# PiZero2W_Hat.net
KiCad netlist of a schematic drawn in Altium Designer
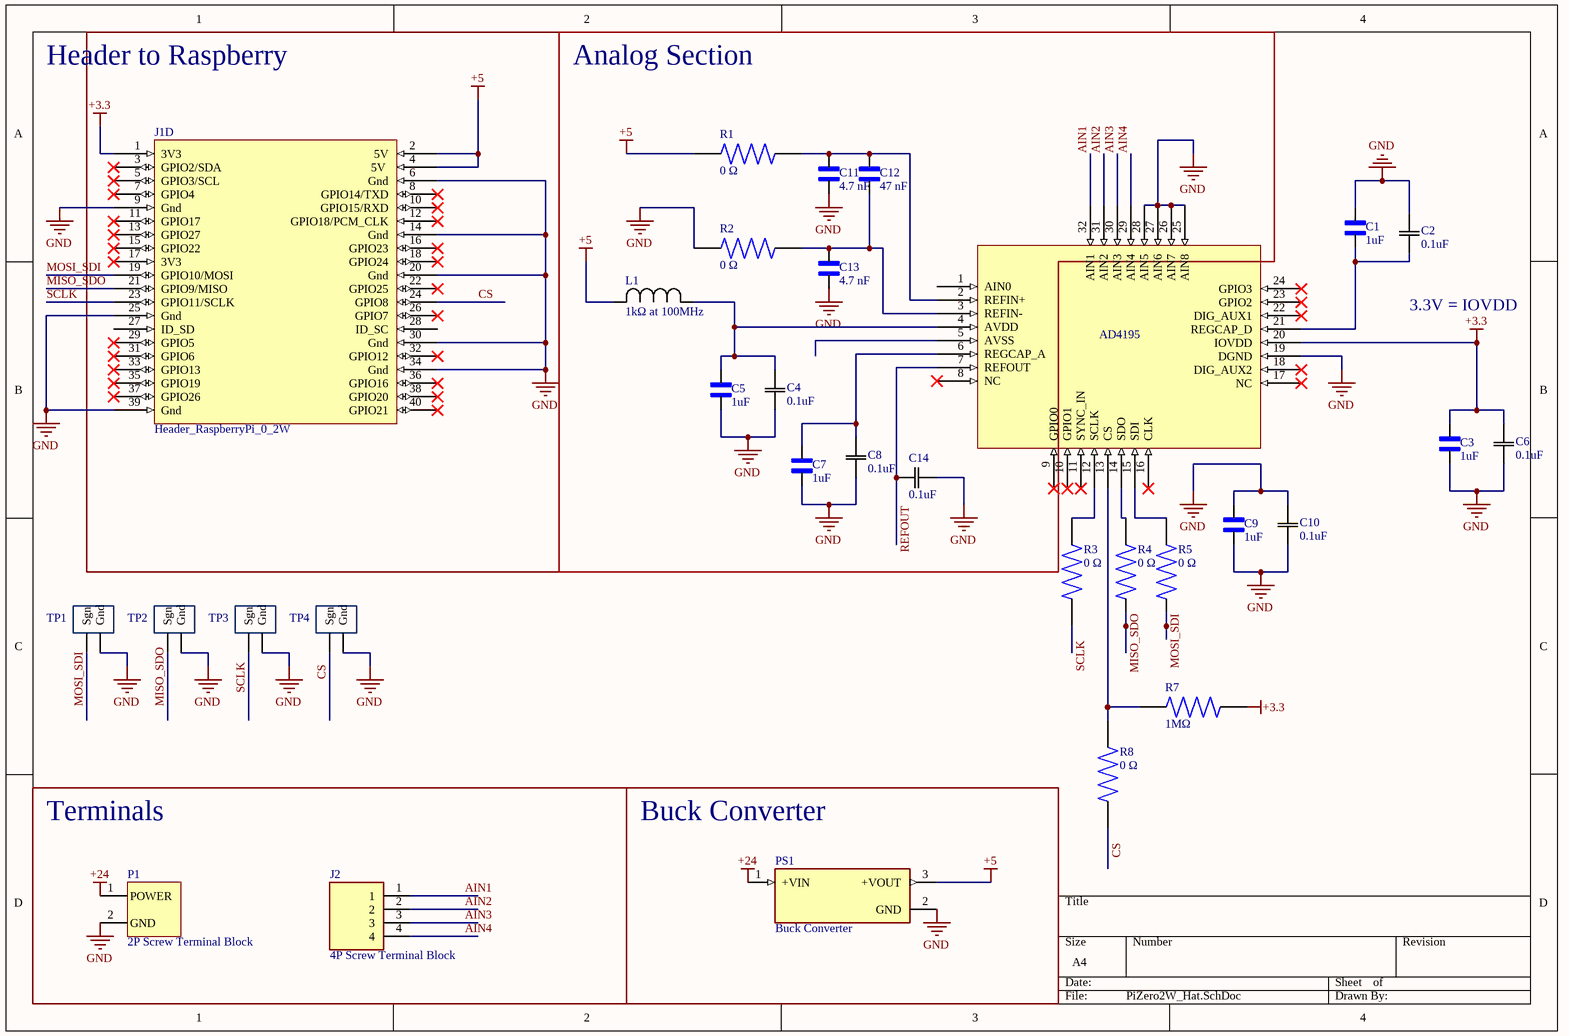
[diagram p0: PiZero2W_Hat.SchDoc]

(export (version "E")
  (design (tool "Eeschema 10.0.6"))
  (components
    (comp (ref "AD4195")
      (value "omponent_1")
      (footprint "QFN50P400X600X80_HS-33N")
      (libsource (lib "RaspberryPi_Zero_2W") (part "Component_1"))
    )
    (comp (ref "C1")
      (value "1uF")
      (footprint "CAPC1608X90N")
      (fields (field (name "MP") "C0603C105K4RACTU"))
      (libsource (lib "C0603C105K4RACTU") (part "C0603C105K4RACTU"))
    )
    (comp (ref "C2")
      (value "0.1uF")
      (footprint "0402_AVX")
      (description "Description")
      (fields
        (field (name "MANUFACTURER_PART_NUMBER") "04023C104KAT2A")
        (field (name "COPYRIGHT") "Copyright (C) 2025 Ultra Librarian. All rights reserved.")
      )
      (libsource (lib "Integrated_Library2") (part "04023C104KAT2A"))
    )
    (comp (ref "C3")
      (value "1uF")
      (footprint "CAPC1608X90N")
      (fields (field (name "MP") "C0603C105K4RACTU"))
      (libsource (lib "C0603C105K4RACTU") (part "C0603C105K4RACTU"))
    )
    (comp (ref "C4")
      (value "0.1uF")
      (footprint "0402_AVX")
      (description "Description")
      (fields
        (field (name "MANUFACTURER_PART_NUMBER") "04023C104KAT2A")
        (field (name "COPYRIGHT") "Copyright (C) 2025 Ultra Librarian. All rights reserved.")
      )
      (libsource (lib "Integrated_Library2") (part "04023C104KAT2A"))
    )
    (comp (ref "C5")
      (value "1uF")
      (footprint "CAPC1608X90N")
      (fields (field (name "MP") "C0603C105K4RACTU"))
      (libsource (lib "C0603C105K4RACTU") (part "C0603C105K4RACTU"))
    )
    (comp (ref "C6")
      (value "0.1uF")
      (footprint "0402_AVX")
      (description "Description")
      (fields
        (field (name "MANUFACTURER_PART_NUMBER") "04023C104KAT2A")
        (field (name "COPYRIGHT") "Copyright (C) 2025 Ultra Librarian. All rights reserved.")
      )
      (libsource (lib "Integrated_Library2") (part "04023C104KAT2A"))
    )
    (comp (ref "C7")
      (value "1uF")
      (footprint "CAPC1608X90N")
      (fields (field (name "MP") "C0603C105K4RACTU"))
      (libsource (lib "C0603C105K4RACTU") (part "C0603C105K4RACTU"))
    )
    (comp (ref "C8")
      (value "0.1uF")
      (footprint "0402_AVX")
      (description "Description")
      (fields
        (field (name "MANUFACTURER_PART_NUMBER") "04023C104KAT2A")
        (field (name "COPYRIGHT") "Copyright (C) 2025 Ultra Librarian. All rights reserved.")
      )
      (libsource (lib "Integrated_Library2") (part "04023C104KAT2A"))
    )
    (comp (ref "C9")
      (value "1uF")
      (footprint "CAPC1608X90N")
      (fields (field (name "MP") "C0603C105K4RACTU"))
      (libsource (lib "C0603C105K4RACTU") (part "C0603C105K4RACTU"))
    )
    (comp (ref "C10")
      (value "0.1uF")
      (footprint "0402_AVX")
      (description "Description")
      (fields
        (field (name "MANUFACTURER_PART_NUMBER") "04023C104KAT2A")
        (field (name "COPYRIGHT") "Copyright (C) 2025 Ultra Librarian. All rights reserved.")
      )
      (libsource (lib "Integrated_Library2") (part "04023C104KAT2A"))
    )
    (comp (ref "C11")
      (value "4.7 nF")
      (footprint "CAPC1608X90N")
      (description "0603 4.7 nF 50 V Â±5% Tolerance C0G SMT Multilayer Ceramic Capacitor")
      (fields (field (name "MF") "Murata") (field (name "MP") "GRM1885C1H472JA01D"))
      (libsource (lib "GRM1885C1H472JA01D") (part "GRM1885C1H472JA01D"))
    )
    (comp (ref "C12")
      (value "47 nF")
      (footprint "CAPC1005X55N")
      (description "SMD capacitor X7R(EIA) with capacitance 47000pF Tol.10%. Rated voltage 25Vdc 125C")
      (fields (field (name "MF") "Murata") (field (name "MP") "GRM155R71E473KA88D"))
      (libsource (lib "GRM155R71E473KA88D") (part "GRM155R71E473KA88D"))
    )
    (comp (ref "C13")
      (value "4.7 nF")
      (footprint "CAPC1608X90N")
      (description "0603 4.7 nF 50 V Â±5% Tolerance C0G SMT Multilayer Ceramic Capacitor")
      (fields (field (name "MF") "Murata") (field (name "MP") "GRM1885C1H472JA01D"))
      (libsource (lib "GRM1885C1H472JA01D") (part "GRM1885C1H472JA01D"))
    )
    (comp (ref "C14")
      (value "0.1uF")
      (footprint "0402_AVX")
      (description "Description")
      (fields
        (field (name "MANUFACTURER_PART_NUMBER") "04023C104KAT2A")
        (field (name "COPYRIGHT") "Copyright (C) 2025 Ultra Librarian. All rights reserved.")
      )
      (libsource (lib "Integrated_Library2") (part "04023C104KAT2A"))
    )
    (comp (ref "J1")
      (value "Header_RaspberryPi_0_2W")
      (footprint "Edge Connector")
      (libsource (lib "Header_RaspberryPiZero_2W") (part "Header_RaspberryPi_0_2W"))
    )
    (comp (ref "J2")
      (value "4P Screw Terminal Block")
      (footprint "TE_282834-4")
      (fields (field (name "MF") "TE Connectivity") (field (name "MP") "282834-4"))
      (libsource (lib "282834-4") (part "282834-4"))
    )
    (comp (ref "L1")
      (value "1kΩ at 100MHz")
      (footprint "IND_1608_TDK")
      (description "Description")
      (fields
        (field (name "MANUFACTURER_PART_NUMBER") "MPZ1608S102ATA00")
        (field (name "COPYRIGHT") "Copyright (C) 2025 Ultra Librarian. All rights reserved.")
      )
      (libsource (lib "Integrated_Library2") (part "MPZ1608S102ATA00"))
    )
    (comp (ref "P1")
      (value "2P Screw Terminal Block")
      (footprint "P_Terminal block 3.5mm-pitch")
      (description "Green Straight pin 3.5mm  pitch; P=3.5mm  Screw terminal ROHS")
      (fields (field (name "MFR PART #") "KF350-3.5-2P") (field (name "MANUFACTURER") "Cixi Kefa Elec"))
      (libsource (lib "ECEN5730Lib_2023_05_DS") (part "P_Terminal block"))
    )
    (comp (ref "PS1")
      (value "Buck Converter")
      (footprint "CONV_TSR_2-2450N")
      (fields (field (name "MF") "{'manufacturer': u'Traco Power'}") (field (name "MP") "TSR_2-2450N"))
      (libsource (lib "TSR_2-2450N") (part "TSR_2-2450N"))
    )
    (comp (ref "R1")
      (value "0 Ω")
      (footprint "RES_ERJ-2GE0R00X")
      (fields (field (name "MF") "Panasonic") (field (name "MP") "ERJ-2GE0R00X"))
      (libsource (lib "ERJ-2GE0R00X") (part "ERJ-2GE0R00X"))
    )
    (comp (ref "R2")
      (value "0 Ω")
      (footprint "RES_ERJ-2GE0R00X")
      (fields (field (name "MF") "Panasonic") (field (name "MP") "ERJ-2GE0R00X"))
      (libsource (lib "ERJ-2GE0R00X") (part "ERJ-2GE0R00X"))
    )
    (comp (ref "R3")
      (value "0 Ω")
      (footprint "RES_ERJ-2GE0R00X")
      (fields (field (name "MF") "Panasonic") (field (name "MP") "ERJ-2GE0R00X"))
      (libsource (lib "ERJ-2GE0R00X") (part "ERJ-2GE0R00X"))
    )
    (comp (ref "R4")
      (value "0 Ω")
      (footprint "RES_ERJ-2GE0R00X")
      (fields (field (name "MF") "Panasonic") (field (name "MP") "ERJ-2GE0R00X"))
      (libsource (lib "ERJ-2GE0R00X") (part "ERJ-2GE0R00X"))
    )
    (comp (ref "R5")
      (value "0 Ω")
      (footprint "RES_ERJ-2GE0R00X")
      (fields (field (name "MF") "Panasonic") (field (name "MP") "ERJ-2GE0R00X"))
      (libsource (lib "ERJ-2GE0R00X") (part "ERJ-2GE0R00X"))
    )
    (comp (ref "R7")
      (value "1MΩ")
      (footprint "RES_ERJ2RKF1004X")
      (description "1 MOhms 1% 0.1W, 1/10W Chip Resistor 0402 (1005 Metric) Automotive AEC-Q200 Thick Film")
      (fields (field (name "MF") "Panasonic Electronic") (field (name "MP") "ERJ-2RKF1004X"))
      (libsource (lib "ERJ2RKF1004X") (part "ERJ2RKF1004X"))
    )
    (comp (ref "R8")
      (value "0 Ω")
      (footprint "RES_ERJ-2GE0R00X")
      (fields (field (name "MF") "Panasonic") (field (name "MP") "ERJ-2GE0R00X"))
      (libsource (lib "ERJ-2GE0R00X") (part "ERJ-2GE0R00X"))
    )
    (comp (ref "TP1")
      (value "10x Probe TP")
      (footprint "TP10x_Probe")
      (description "Test Point 300 mil centers")
      (libsource (lib "ECEN5730Lib_2023_05_DS") (part "TP_10x_Probe"))
    )
    (comp (ref "TP2")
      (value "10x Probe TP")
      (footprint "TP10x_Probe")
      (description "Test Point 300 mil centers")
      (libsource (lib "ECEN5730Lib_2023_05_DS") (part "TP_10x_Probe"))
    )
    (comp (ref "TP3")
      (value "10x Probe TP")
      (footprint "TP10x_Probe")
      (description "Test Point 300 mil centers")
      (libsource (lib "ECEN5730Lib_2023_05_DS") (part "TP_10x_Probe"))
    )
    (comp (ref "TP4")
      (value "10x Probe TP")
      (footprint "TP10x_Probe")
      (description "Test Point 300 mil centers")
      (libsource (lib "ECEN5730Lib_2023_05_DS") (part "TP_10x_Probe"))
    )
  )
  (nets
    (net (code "1") (name "+3.3") (class "Default")
      (node (ref "AD4195") (pin "20") (pinfunction "IOVDD_20") (pintype "input"))
      (node (ref "C3") (pin "2") (pinfunction "2_2") (pintype "passive"))
      (node (ref "C6") (pin "2") (pinfunction "2_2") (pintype "passive"))
      (node (ref "J1") (pin "1") (pinfunction "3V3_1") (pintype "input"))
      (node (ref "R7") (pin "2") (pinfunction "2_2") (pintype "passive"))
    )
    (net (code "2") (name "+5") (class "Default")
      (node (ref "J1") (pin "2") (pinfunction "5V_2") (pintype "input"))
      (node (ref "J1") (pin "4") (pinfunction "5V_4") (pintype "input"))
      (node (ref "L1") (pin "2") (pinfunction "2_2") (pintype "passive"))
      (node (ref "PS1") (pin "3") (pinfunction "+VOUT_3") (pintype "output"))
      (node (ref "R1") (pin "2") (pinfunction "2_2") (pintype "passive"))
    )
    (net (code "3") (name "+24") (class "Default")
      (node (ref "P1") (pin "1") (pinfunction "POWER_1") (pintype "passive"))
      (node (ref "PS1") (pin "1") (pinfunction "+VIN_1") (pintype "input"))
    )
    (net (code "4") (name "/AIN1") (class "Default")
      (node (ref "AD4195") (pin "32") (pinfunction "AIN1_32") (pintype "input"))
      (node (ref "J2") (pin "1") (pinfunction "1_1") (pintype "passive"))
    )
    (net (code "5") (name "/AIN2") (class "Default")
      (node (ref "AD4195") (pin "31") (pinfunction "AIN2_31") (pintype "input"))
      (node (ref "J2") (pin "2") (pinfunction "2_2") (pintype "passive"))
    )
    (net (code "6") (name "/AIN3") (class "Default")
      (node (ref "AD4195") (pin "30") (pinfunction "AIN3_30") (pintype "input"))
      (node (ref "J2") (pin "3") (pinfunction "3_3") (pintype "passive"))
    )
    (net (code "7") (name "/AIN4") (class "Default")
      (node (ref "AD4195") (pin "29") (pinfunction "AIN4_29") (pintype "input"))
      (node (ref "J2") (pin "4") (pinfunction "4_4") (pintype "passive"))
    )
    (net (code "8") (name "/CS") (class "Default")
      (node (ref "J1") (pin "24") (pinfunction "GPIO8_24") (pintype "bidirectional"))
      (node (ref "R8") (pin "1") (pinfunction "1_1") (pintype "passive"))
      (node (ref "TP4") (pin "1") (pinfunction "Sgn_1") (pintype "passive"))
    )
    (net (code "9") (name "/MISO_SDO") (class "Default")
      (node (ref "J1") (pin "21") (pinfunction "GPIO9/MISO_21") (pintype "bidirectional"))
      (node (ref "R4") (pin "1") (pinfunction "1_1") (pintype "passive"))
      (node (ref "TP2") (pin "1") (pinfunction "Sgn_1") (pintype "passive"))
    )
    (net (code "10") (name "/MOSI_SDI") (class "Default")
      (node (ref "J1") (pin "19") (pinfunction "GPIO10/MOSI_19") (pintype "bidirectional"))
      (node (ref "R5") (pin "1") (pinfunction "1_1") (pintype "passive"))
      (node (ref "TP1") (pin "1") (pinfunction "Sgn_1") (pintype "passive"))
    )
    (net (code "11") (name "/REFOUT") (class "Default")
      (node (ref "AD4195") (pin "7") (pinfunction "REFOUT_7") (pintype "input"))
      (node (ref "C14") (pin "2") (pinfunction "2_2") (pintype "passive"))
    )
    (net (code "12") (name "/SCLK") (class "Default")
      (node (ref "J1") (pin "23") (pinfunction "GPIO11/SCLK_23") (pintype "bidirectional"))
      (node (ref "R3") (pin "1") (pinfunction "1_1") (pintype "passive"))
      (node (ref "TP3") (pin "1") (pinfunction "Sgn_1") (pintype "passive"))
    )
    (net (code "13") (name "GND") (class "Default")
      (node (ref "AD4195") (pin "19") (pinfunction "DGND_19") (pintype "input"))
      (node (ref "AD4195") (pin "25") (pinfunction "AIN8_25") (pintype "input"))
      (node (ref "AD4195") (pin "26") (pinfunction "AIN7_26") (pintype "input"))
      (node (ref "AD4195") (pin "27") (pinfunction "AIN6_27") (pintype "input"))
      (node (ref "AD4195") (pin "28") (pinfunction "AIN5_28") (pintype "input"))
      (node (ref "C1") (pin "2") (pinfunction "2_2") (pintype "passive"))
      (node (ref "C10") (pin "1") (pinfunction "1_1") (pintype "passive"))
      (node (ref "C10") (pin "2") (pinfunction "2_2") (pintype "passive"))
      (node (ref "C11") (pin "1") (pinfunction "1_1") (pintype "passive"))
      (node (ref "C13") (pin "1") (pinfunction "1_1") (pintype "passive"))
      (node (ref "C14") (pin "1") (pinfunction "1_1") (pintype "passive"))
      (node (ref "C2") (pin "2") (pinfunction "2_2") (pintype "passive"))
      (node (ref "C3") (pin "1") (pinfunction "1_1") (pintype "passive"))
      (node (ref "C4") (pin "1") (pinfunction "1_1") (pintype "passive"))
      (node (ref "C5") (pin "1") (pinfunction "1_1") (pintype "passive"))
      (node (ref "C6") (pin "1") (pinfunction "1_1") (pintype "passive"))
      (node (ref "C7") (pin "1") (pinfunction "1_1") (pintype "passive"))
      (node (ref "C8") (pin "1") (pinfunction "1_1") (pintype "passive"))
      (node (ref "C9") (pin "1") (pinfunction "1_1") (pintype "passive"))
      (node (ref "C9") (pin "2") (pinfunction "2_2") (pintype "passive"))
      (node (ref "J1") (pin "14") (pinfunction "Gnd_14") (pintype "input"))
      (node (ref "J1") (pin "20") (pinfunction "Gnd_20") (pintype "input"))
      (node (ref "J1") (pin "25") (pinfunction "Gnd_25") (pintype "input"))
      (node (ref "J1") (pin "30") (pinfunction "Gnd_30") (pintype "input"))
      (node (ref "J1") (pin "34") (pinfunction "Gnd_34") (pintype "input"))
      (node (ref "J1") (pin "39") (pinfunction "Gnd_39") (pintype "input"))
      (node (ref "J1") (pin "6") (pinfunction "Gnd_6") (pintype "input"))
      (node (ref "J1") (pin "9") (pinfunction "Gnd_9") (pintype "input"))
      (node (ref "P1") (pin "2") (pinfunction "GND_2") (pintype "passive"))
      (node (ref "PS1") (pin "2") (pinfunction "GND_2") (pintype "power_in"))
      (node (ref "R2") (pin "2") (pinfunction "2_2") (pintype "passive"))
      (node (ref "TP1") (pin "2") (pinfunction "Gnd_2") (pintype "passive"))
      (node (ref "TP2") (pin "2") (pinfunction "Gnd_2") (pintype "passive"))
      (node (ref "TP3") (pin "2") (pinfunction "Gnd_2") (pintype "passive"))
      (node (ref "TP4") (pin "2") (pinfunction "Gnd_2") (pintype "passive"))
    )
    (net (code "14") (name "Net-(AD4195-AVDD)") (class "Default")
      (node (ref "AD4195") (pin "4") (pinfunction "AVDD_4") (pintype "input"))
      (node (ref "C4") (pin "2") (pinfunction "2_2") (pintype "passive"))
      (node (ref "C5") (pin "2") (pinfunction "2_2") (pintype "passive"))
      (node (ref "L1") (pin "1") (pinfunction "1_1") (pintype "passive"))
    )
    (net (code "15") (name "Net-(AD4195-CS)") (class "Default")
      (node (ref "AD4195") (pin "13") (pinfunction "CS_13") (pintype "input"))
      (node (ref "R7") (pin "1") (pinfunction "1_1") (pintype "passive"))
      (node (ref "R8") (pin "2") (pinfunction "2_2") (pintype "passive"))
    )
    (net (code "16") (name "Net-(AD4195-REFIN+)") (class "Default")
      (node (ref "AD4195") (pin "2") (pinfunction "REFIN+_2") (pintype "input"))
      (node (ref "C11") (pin "2") (pinfunction "2_2") (pintype "passive"))
      (node (ref "C12") (pin "2") (pinfunction "2_2") (pintype "passive"))
      (node (ref "R1") (pin "1") (pinfunction "1_1") (pintype "passive"))
    )
    (net (code "17") (name "Net-(AD4195-REFIN-)") (class "Default")
      (node (ref "AD4195") (pin "3") (pinfunction "REFIN-_3") (pintype "input"))
      (node (ref "C12") (pin "1") (pinfunction "1_1") (pintype "passive"))
      (node (ref "C13") (pin "2") (pinfunction "2_2") (pintype "passive"))
      (node (ref "R2") (pin "1") (pinfunction "1_1") (pintype "passive"))
    )
    (net (code "18") (name "Net-(AD4195-REGCAP_A)") (class "Default")
      (node (ref "AD4195") (pin "6") (pinfunction "REGCAP_A_6") (pintype "input"))
      (node (ref "C7") (pin "2") (pinfunction "2_2") (pintype "passive"))
      (node (ref "C8") (pin "2") (pinfunction "2_2") (pintype "passive"))
    )
    (net (code "19") (name "Net-(AD4195-REGCAP_D)") (class "Default")
      (node (ref "AD4195") (pin "21") (pinfunction "REGCAP_D_21") (pintype "input"))
      (node (ref "C1") (pin "1") (pinfunction "1_1") (pintype "passive"))
      (node (ref "C2") (pin "1") (pinfunction "1_1") (pintype "passive"))
    )
    (net (code "20") (name "Net-(AD4195-SCLK)") (class "Default")
      (node (ref "AD4195") (pin "12") (pinfunction "SCLK_12") (pintype "input"))
      (node (ref "R3") (pin "2") (pinfunction "2_2") (pintype "passive"))
    )
    (net (code "21") (name "Net-(AD4195-SDI)") (class "Default")
      (node (ref "AD4195") (pin "15") (pinfunction "SDI_15") (pintype "input"))
      (node (ref "R5") (pin "2") (pinfunction "2_2") (pintype "passive"))
    )
    (net (code "22") (name "Net-(AD4195-SDO)") (class "Default")
      (node (ref "AD4195") (pin "14") (pinfunction "SDO_14") (pintype "input"))
      (node (ref "R4") (pin "2") (pinfunction "2_2") (pintype "passive"))
    )
    (net (code "23") (name "unconnected-(AD4195-AIN0-Pad1)") (class "Default")
      (node (ref "AD4195") (pin "1") (pinfunction "AIN0_1") (pintype "input"))
    )
    (net (code "24") (name "unconnected-(AD4195-AVSS-Pad5)") (class "Default")
      (node (ref "AD4195") (pin "5") (pinfunction "AVSS_5") (pintype "input"))
    )
    (net (code "25") (name "unconnected-(AD4195-CLK-Pad16)") (class "Default")
      (node (ref "AD4195") (pin "16") (pinfunction "CLK_16") (pintype "input+no_connect"))
    )
    (net (code "26") (name "unconnected-(AD4195-DIG_AUX1-Pad22)") (class "Default")
      (node (ref "AD4195") (pin "22") (pinfunction "DIG_AUX1_22") (pintype "input+no_connect"))
    )
    (net (code "27") (name "unconnected-(AD4195-DIG_AUX2-Pad18)") (class "Default")
      (node (ref "AD4195") (pin "18") (pinfunction "DIG_AUX2_18") (pintype "input+no_connect"))
    )
    (net (code "28") (name "unconnected-(AD4195-GPIO0-Pad9)") (class "Default")
      (node (ref "AD4195") (pin "9") (pinfunction "GPIO0_9") (pintype "input+no_connect"))
    )
    (net (code "29") (name "unconnected-(AD4195-GPIO1-Pad10)") (class "Default")
      (node (ref "AD4195") (pin "10") (pinfunction "GPIO1_10") (pintype "input+no_connect"))
    )
    (net (code "30") (name "unconnected-(AD4195-GPIO2-Pad23)") (class "Default")
      (node (ref "AD4195") (pin "23") (pinfunction "GPIO2_23") (pintype "input+no_connect"))
    )
    (net (code "31") (name "unconnected-(AD4195-GPIO3-Pad24)") (class "Default")
      (node (ref "AD4195") (pin "24") (pinfunction "GPIO3_24") (pintype "input+no_connect"))
    )
    (net (code "32") (name "unconnected-(AD4195-NC-Pad8)") (class "Default")
      (node (ref "AD4195") (pin "8") (pinfunction "NC_8") (pintype "input+no_connect"))
    )
    (net (code "33") (name "unconnected-(AD4195-NC-Pad17)") (class "Default")
      (node (ref "AD4195") (pin "17") (pinfunction "NC_17") (pintype "input+no_connect"))
    )
    (net (code "34") (name "unconnected-(AD4195-SYNC_IN-Pad11)") (class "Default")
      (node (ref "AD4195") (pin "11") (pinfunction "SYNC_IN_11") (pintype "input+no_connect"))
    )
    (net (code "35") (name "unconnected-(J1D-3V3-Pad17)") (class "Default")
      (node (ref "J1") (pin "17") (pinfunction "3V3_17") (pintype "input+no_connect"))
    )
    (net (code "36") (name "unconnected-(J1D-GPIO2{slash}SDA-Pad3)") (class "Default")
      (node (ref "J1") (pin "3") (pinfunction "GPIO2/SDA_3") (pintype "bidirectional+no_connect"))
    )
    (net (code "37") (name "unconnected-(J1D-GPIO3{slash}SCL-Pad5)") (class "Default")
      (node (ref "J1") (pin "5") (pinfunction "GPIO3/SCL_5") (pintype "bidirectional+no_connect"))
    )
    (net (code "38") (name "unconnected-(J1D-GPIO4-Pad7)") (class "Default")
      (node (ref "J1") (pin "7") (pinfunction "GPIO4_7") (pintype "bidirectional+no_connect"))
    )
    (net (code "39") (name "unconnected-(J1D-GPIO5-Pad29)") (class "Default")
      (node (ref "J1") (pin "29") (pinfunction "GPIO5_29") (pintype "bidirectional+no_connect"))
    )
    (net (code "40") (name "unconnected-(J1D-GPIO6-Pad31)") (class "Default")
      (node (ref "J1") (pin "31") (pinfunction "GPIO6_31") (pintype "bidirectional+no_connect"))
    )
    (net (code "41") (name "unconnected-(J1D-GPIO7-Pad26)") (class "Default")
      (node (ref "J1") (pin "26") (pinfunction "GPIO7_26") (pintype "bidirectional+no_connect"))
    )
    (net (code "42") (name "unconnected-(J1D-GPIO12-Pad32)") (class "Default")
      (node (ref "J1") (pin "32") (pinfunction "GPIO12_32") (pintype "bidirectional+no_connect"))
    )
    (net (code "43") (name "unconnected-(J1D-GPIO13-Pad33)") (class "Default")
      (node (ref "J1") (pin "33") (pinfunction "GPIO13_33") (pintype "bidirectional+no_connect"))
    )
    (net (code "44") (name "unconnected-(J1D-GPIO14{slash}TXD-Pad8)") (class "Default")
      (node (ref "J1") (pin "8") (pinfunction "GPIO14/TXD_8") (pintype "bidirectional+no_connect"))
    )
    (net (code "45") (name "unconnected-(J1D-GPIO15{slash}RXD-Pad10)") (class "Default")
      (node (ref "J1") (pin "10") (pinfunction "GPIO15/RXD_10") (pintype "bidirectional+no_connect"))
    )
    (net (code "46") (name "unconnected-(J1D-GPIO16-Pad36)") (class "Default")
      (node (ref "J1") (pin "36") (pinfunction "GPIO16_36") (pintype "bidirectional+no_connect"))
    )
    (net (code "47") (name "unconnected-(J1D-GPIO17-Pad11)") (class "Default")
      (node (ref "J1") (pin "11") (pinfunction "GPIO17_11") (pintype "bidirectional+no_connect"))
    )
    (net (code "48") (name "unconnected-(J1D-GPIO18{slash}PCM_CLK-Pad12)") (class "Default")
      (node (ref "J1") (pin "12") (pinfunction "GPIO18/PCM_CLK_12") (pintype "input+no_connect"))
    )
    (net (code "49") (name "unconnected-(J1D-GPIO19-Pad35)") (class "Default")
      (node (ref "J1") (pin "35") (pinfunction "GPIO19_35") (pintype "bidirectional+no_connect"))
    )
    (net (code "50") (name "unconnected-(J1D-GPIO20-Pad38)") (class "Default")
      (node (ref "J1") (pin "38") (pinfunction "GPIO20_38") (pintype "bidirectional+no_connect"))
    )
    (net (code "51") (name "unconnected-(J1D-GPIO21-Pad40)") (class "Default")
      (node (ref "J1") (pin "40") (pinfunction "GPIO21_40") (pintype "bidirectional+no_connect"))
    )
    (net (code "52") (name "unconnected-(J1D-GPIO22-Pad15)") (class "Default")
      (node (ref "J1") (pin "15") (pinfunction "GPIO22_15") (pintype "bidirectional+no_connect"))
    )
    (net (code "53") (name "unconnected-(J1D-GPIO23-Pad16)") (class "Default")
      (node (ref "J1") (pin "16") (pinfunction "GPIO23_16") (pintype "bidirectional+no_connect"))
    )
    (net (code "54") (name "unconnected-(J1D-GPIO24-Pad18)") (class "Default")
      (node (ref "J1") (pin "18") (pinfunction "GPIO24_18") (pintype "bidirectional+no_connect"))
    )
    (net (code "55") (name "unconnected-(J1D-GPIO25-Pad22)") (class "Default")
      (node (ref "J1") (pin "22") (pinfunction "GPIO25_22") (pintype "bidirectional+no_connect"))
    )
    (net (code "56") (name "unconnected-(J1D-GPIO26-Pad37)") (class "Default")
      (node (ref "J1") (pin "37") (pinfunction "GPIO26_37") (pintype "bidirectional+no_connect"))
    )
    (net (code "57") (name "unconnected-(J1D-GPIO27-Pad13)") (class "Default")
      (node (ref "J1") (pin "13") (pinfunction "GPIO27_13") (pintype "bidirectional+no_connect"))
    )
    (net (code "58") (name "unconnected-(J1D-ID_SC-Pad28)") (class "Default")
      (node (ref "J1") (pin "28") (pinfunction "ID_SC_28") (pintype "input"))
    )
    (net (code "59") (name "unconnected-(J1D-ID_SD-Pad27)") (class "Default")
      (node (ref "J1") (pin "27") (pinfunction "ID_SD_27") (pintype "input"))
    )
  )
)
